# 7SegDisplay.net
KiCad netlist of a schematic drawn in Altium Designer
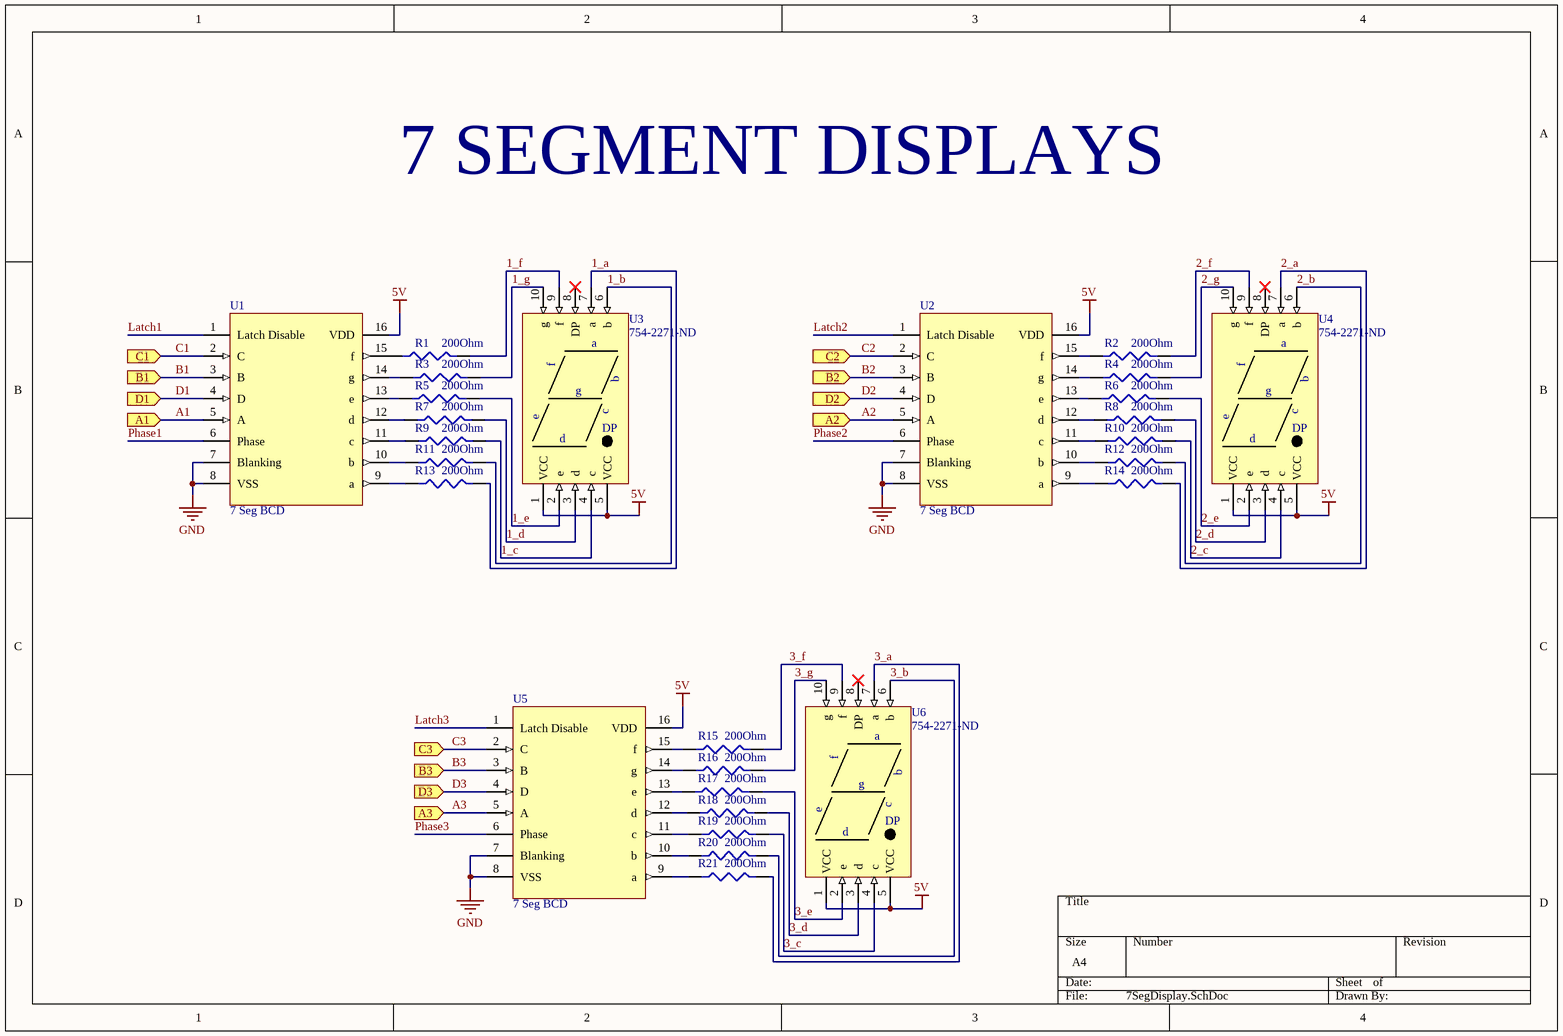
[diagram p0: 7SegDisplay.SchDoc]

(export (version "E")
  (design (tool "Eeschema 10.0.6"))
  (components
    (comp (ref "R1")
      (value "200Ohm")
      (footprint "RES-0805")
      (description "RES SMD 200 OHM 1% 1/4W 0805")
      (fields
        (field (name "MANUFACTURER") "Stackpole Electronics")
        (field (name "MANUFACTURER PART NUMBER") "RNCP0805FTD200R")
      )
      (libsource (lib "Dashboard") (part "RNCP0805FTD200R"))
    )
    (comp (ref "R2")
      (value "200Ohm")
      (footprint "RES-0805")
      (description "RES SMD 200 OHM 1% 1/4W 0805")
      (fields
        (field (name "MANUFACTURER") "Stackpole Electronics")
        (field (name "MANUFACTURER PART NUMBER") "RNCP0805FTD200R")
      )
      (libsource (lib "Dashboard") (part "RNCP0805FTD200R"))
    )
    (comp (ref "R3")
      (value "200Ohm")
      (footprint "RES-0805")
      (description "RES SMD 200 OHM 1% 1/4W 0805")
      (fields
        (field (name "MANUFACTURER") "Stackpole Electronics")
        (field (name "MANUFACTURER PART NUMBER") "RNCP0805FTD200R")
      )
      (libsource (lib "Dashboard") (part "RNCP0805FTD200R"))
    )
    (comp (ref "R4")
      (value "200Ohm")
      (footprint "RES-0805")
      (description "RES SMD 200 OHM 1% 1/4W 0805")
      (fields
        (field (name "MANUFACTURER") "Stackpole Electronics")
        (field (name "MANUFACTURER PART NUMBER") "RNCP0805FTD200R")
      )
      (libsource (lib "Dashboard") (part "RNCP0805FTD200R"))
    )
    (comp (ref "R5")
      (value "200Ohm")
      (footprint "RES-0805")
      (description "RES SMD 200 OHM 1% 1/4W 0805")
      (fields
        (field (name "MANUFACTURER") "Stackpole Electronics")
        (field (name "MANUFACTURER PART NUMBER") "RNCP0805FTD200R")
      )
      (libsource (lib "Dashboard") (part "RNCP0805FTD200R"))
    )
    (comp (ref "R6")
      (value "200Ohm")
      (footprint "RES-0805")
      (description "RES SMD 200 OHM 1% 1/4W 0805")
      (fields
        (field (name "MANUFACTURER") "Stackpole Electronics")
        (field (name "MANUFACTURER PART NUMBER") "RNCP0805FTD200R")
      )
      (libsource (lib "Dashboard") (part "RNCP0805FTD200R"))
    )
    (comp (ref "R7")
      (value "200Ohm")
      (footprint "RES-0805")
      (description "RES SMD 200 OHM 1% 1/4W 0805")
      (fields
        (field (name "MANUFACTURER") "Stackpole Electronics")
        (field (name "MANUFACTURER PART NUMBER") "RNCP0805FTD200R")
      )
      (libsource (lib "Dashboard") (part "RNCP0805FTD200R"))
    )
    (comp (ref "R8")
      (value "200Ohm")
      (footprint "RES-0805")
      (description "RES SMD 200 OHM 1% 1/4W 0805")
      (fields
        (field (name "MANUFACTURER") "Stackpole Electronics")
        (field (name "MANUFACTURER PART NUMBER") "RNCP0805FTD200R")
      )
      (libsource (lib "Dashboard") (part "RNCP0805FTD200R"))
    )
    (comp (ref "R9")
      (value "200Ohm")
      (footprint "RES-0805")
      (description "RES SMD 200 OHM 1% 1/4W 0805")
      (fields
        (field (name "MANUFACTURER") "Stackpole Electronics")
        (field (name "MANUFACTURER PART NUMBER") "RNCP0805FTD200R")
      )
      (libsource (lib "Dashboard") (part "RNCP0805FTD200R"))
    )
    (comp (ref "R10")
      (value "200Ohm")
      (footprint "RES-0805")
      (description "RES SMD 200 OHM 1% 1/4W 0805")
      (fields
        (field (name "MANUFACTURER") "Stackpole Electronics")
        (field (name "MANUFACTURER PART NUMBER") "RNCP0805FTD200R")
      )
      (libsource (lib "Dashboard") (part "RNCP0805FTD200R"))
    )
    (comp (ref "R11")
      (value "200Ohm")
      (footprint "RES-0805")
      (description "RES SMD 200 OHM 1% 1/4W 0805")
      (fields
        (field (name "MANUFACTURER") "Stackpole Electronics")
        (field (name "MANUFACTURER PART NUMBER") "RNCP0805FTD200R")
      )
      (libsource (lib "Dashboard") (part "RNCP0805FTD200R"))
    )
    (comp (ref "R12")
      (value "200Ohm")
      (footprint "RES-0805")
      (description "RES SMD 200 OHM 1% 1/4W 0805")
      (fields
        (field (name "MANUFACTURER") "Stackpole Electronics")
        (field (name "MANUFACTURER PART NUMBER") "RNCP0805FTD200R")
      )
      (libsource (lib "Dashboard") (part "RNCP0805FTD200R"))
    )
    (comp (ref "R13")
      (value "200Ohm")
      (footprint "RES-0805")
      (description "RES SMD 200 OHM 1% 1/4W 0805")
      (fields
        (field (name "MANUFACTURER") "Stackpole Electronics")
        (field (name "MANUFACTURER PART NUMBER") "RNCP0805FTD200R")
      )
      (libsource (lib "Dashboard") (part "RNCP0805FTD200R"))
    )
    (comp (ref "R14")
      (value "200Ohm")
      (footprint "RES-0805")
      (description "RES SMD 200 OHM 1% 1/4W 0805")
      (fields
        (field (name "MANUFACTURER") "Stackpole Electronics")
        (field (name "MANUFACTURER PART NUMBER") "RNCP0805FTD200R")
      )
      (libsource (lib "Dashboard") (part "RNCP0805FTD200R"))
    )
    (comp (ref "R15")
      (value "200Ohm")
      (footprint "RES-0805")
      (description "RES SMD 200 OHM 1% 1/4W 0805")
      (fields
        (field (name "MANUFACTURER") "Stackpole Electronics")
        (field (name "MANUFACTURER PART NUMBER") "RNCP0805FTD200R")
      )
      (libsource (lib "Dashboard") (part "RNCP0805FTD200R"))
    )
    (comp (ref "R16")
      (value "200Ohm")
      (footprint "RES-0805")
      (description "RES SMD 200 OHM 1% 1/4W 0805")
      (fields
        (field (name "MANUFACTURER") "Stackpole Electronics")
        (field (name "MANUFACTURER PART NUMBER") "RNCP0805FTD200R")
      )
      (libsource (lib "Dashboard") (part "RNCP0805FTD200R"))
    )
    (comp (ref "R17")
      (value "200Ohm")
      (footprint "RES-0805")
      (description "RES SMD 200 OHM 1% 1/4W 0805")
      (fields
        (field (name "MANUFACTURER") "Stackpole Electronics")
        (field (name "MANUFACTURER PART NUMBER") "RNCP0805FTD200R")
      )
      (libsource (lib "Dashboard") (part "RNCP0805FTD200R"))
    )
    (comp (ref "R18")
      (value "200Ohm")
      (footprint "RES-0805")
      (description "RES SMD 200 OHM 1% 1/4W 0805")
      (fields
        (field (name "MANUFACTURER") "Stackpole Electronics")
        (field (name "MANUFACTURER PART NUMBER") "RNCP0805FTD200R")
      )
      (libsource (lib "Dashboard") (part "RNCP0805FTD200R"))
    )
    (comp (ref "R19")
      (value "200Ohm")
      (footprint "RES-0805")
      (description "RES SMD 200 OHM 1% 1/4W 0805")
      (fields
        (field (name "MANUFACTURER") "Stackpole Electronics")
        (field (name "MANUFACTURER PART NUMBER") "RNCP0805FTD200R")
      )
      (libsource (lib "Dashboard") (part "RNCP0805FTD200R"))
    )
    (comp (ref "R20")
      (value "200Ohm")
      (footprint "RES-0805")
      (description "RES SMD 200 OHM 1% 1/4W 0805")
      (fields
        (field (name "MANUFACTURER") "Stackpole Electronics")
        (field (name "MANUFACTURER PART NUMBER") "RNCP0805FTD200R")
      )
      (libsource (lib "Dashboard") (part "RNCP0805FTD200R"))
    )
    (comp (ref "R21")
      (value "200Ohm")
      (footprint "RES-0805")
      (description "RES SMD 200 OHM 1% 1/4W 0805")
      (fields
        (field (name "MANUFACTURER") "Stackpole Electronics")
        (field (name "MANUFACTURER PART NUMBER") "RNCP0805FTD200R")
      )
      (libsource (lib "Dashboard") (part "RNCP0805FTD200R"))
    )
    (comp (ref "U1")
      (value "7 Seg BCD")
      (footprint "TSOP65P640X120-16N")
      (description "IC BCD7SEG LCH/DECD/DRVR 16TSSOP")
      (fields
        (field (name "MANUFACTURER") "Texas Instruments")
        (field (name "MANUFACTURER PART NUMBER") "CD4543BPWR")
      )
      (libsource (lib "Dashboard") (part "CD4543BPWR"))
    )
    (comp (ref "U2")
      (value "7 Seg BCD")
      (footprint "TSOP65P640X120-16N")
      (description "IC BCD7SEG LCH/DECD/DRVR 16TSSOP")
      (fields
        (field (name "MANUFACTURER") "Texas Instruments")
        (field (name "MANUFACTURER PART NUMBER") "CD4543BPWR")
      )
      (libsource (lib "Dashboard") (part "CD4543BPWR"))
    )
    (comp (ref "U3")
      (value "754-2271-ND")
      (footprint "SA15-11EWA")
      (description "DISPLAY, SEVEN SEGMENT, 47MM, RED, COMMON ANODE")
      (fields
        (field (name "MANUFACTURER") "Kingbright")
        (field (name "MANUFACTURER PART NUMBER") "SA15-11EWA")
      )
      (libsource (lib "Dashboard") (part "SA15-11EWA"))
    )
    (comp (ref "U4")
      (value "754-2271-ND")
      (footprint "SA15-11EWA")
      (description "DISPLAY, SEVEN SEGMENT, 47MM, RED, COMMON ANODE")
      (fields
        (field (name "MANUFACTURER") "Kingbright")
        (field (name "MANUFACTURER PART NUMBER") "SA15-11EWA")
      )
      (libsource (lib "Dashboard") (part "SA15-11EWA"))
    )
    (comp (ref "U5")
      (value "7 Seg BCD")
      (footprint "TSOP65P640X120-16N")
      (description "IC BCD7SEG LCH/DECD/DRVR 16TSSOP")
      (fields
        (field (name "MANUFACTURER") "Texas Instruments")
        (field (name "MANUFACTURER PART NUMBER") "CD4543BPWR")
      )
      (libsource (lib "Dashboard") (part "CD4543BPWR"))
    )
    (comp (ref "U6")
      (value "754-2271-ND")
      (footprint "SA15-11EWA")
      (description "DISPLAY, SEVEN SEGMENT, 47MM, RED, COMMON ANODE")
      (fields
        (field (name "MANUFACTURER") "Kingbright")
        (field (name "MANUFACTURER PART NUMBER") "SA15-11EWA")
      )
      (libsource (lib "Dashboard") (part "SA15-11EWA"))
    )
  )
  (nets
    (net (code "1") (name "/1_a") (class "Default")
      (node (ref "R13") (pin "2") (pinfunction "2_2") (pintype "passive"))
      (node (ref "U3") (pin "7") (pinfunction "a_7") (pintype "input"))
    )
    (net (code "2") (name "/1_b") (class "Default")
      (node (ref "R11") (pin "2") (pinfunction "2_2") (pintype "passive"))
      (node (ref "U3") (pin "6") (pinfunction "b_6") (pintype "input"))
    )
    (net (code "3") (name "/1_c") (class "Default")
      (node (ref "R9") (pin "2") (pinfunction "2_2") (pintype "passive"))
      (node (ref "U3") (pin "4") (pinfunction "c_4") (pintype "input"))
    )
    (net (code "4") (name "/1_d") (class "Default")
      (node (ref "R7") (pin "2") (pinfunction "2_2") (pintype "passive"))
      (node (ref "U3") (pin "3") (pinfunction "d_3") (pintype "input"))
    )
    (net (code "5") (name "/1_e") (class "Default")
      (node (ref "R5") (pin "2") (pinfunction "2_2") (pintype "passive"))
      (node (ref "U3") (pin "2") (pinfunction "e_2") (pintype "input"))
    )
    (net (code "6") (name "/1_f") (class "Default")
      (node (ref "R1") (pin "2") (pinfunction "2_2") (pintype "passive"))
      (node (ref "U3") (pin "9") (pinfunction "f_9") (pintype "input"))
    )
    (net (code "7") (name "/1_g") (class "Default")
      (node (ref "R3") (pin "2") (pinfunction "2_2") (pintype "passive"))
      (node (ref "U3") (pin "10") (pinfunction "g_10") (pintype "input"))
    )
    (net (code "8") (name "/2_a") (class "Default")
      (node (ref "R14") (pin "2") (pinfunction "2_2") (pintype "passive"))
      (node (ref "U4") (pin "7") (pinfunction "a_7") (pintype "input"))
    )
    (net (code "9") (name "/2_b") (class "Default")
      (node (ref "R12") (pin "2") (pinfunction "2_2") (pintype "passive"))
      (node (ref "U4") (pin "6") (pinfunction "b_6") (pintype "input"))
    )
    (net (code "10") (name "/2_c") (class "Default")
      (node (ref "R10") (pin "2") (pinfunction "2_2") (pintype "passive"))
      (node (ref "U4") (pin "4") (pinfunction "c_4") (pintype "input"))
    )
    (net (code "11") (name "/2_d") (class "Default")
      (node (ref "R8") (pin "2") (pinfunction "2_2") (pintype "passive"))
      (node (ref "U4") (pin "3") (pinfunction "d_3") (pintype "input"))
    )
    (net (code "12") (name "/2_e") (class "Default")
      (node (ref "R6") (pin "2") (pinfunction "2_2") (pintype "passive"))
      (node (ref "U4") (pin "2") (pinfunction "e_2") (pintype "input"))
    )
    (net (code "13") (name "/2_f") (class "Default")
      (node (ref "R2") (pin "2") (pinfunction "2_2") (pintype "passive"))
      (node (ref "U4") (pin "9") (pinfunction "f_9") (pintype "input"))
    )
    (net (code "14") (name "/2_g") (class "Default")
      (node (ref "R4") (pin "2") (pinfunction "2_2") (pintype "passive"))
      (node (ref "U4") (pin "10") (pinfunction "g_10") (pintype "input"))
    )
    (net (code "15") (name "/3_a") (class "Default")
      (node (ref "R21") (pin "2") (pinfunction "2_2") (pintype "passive"))
      (node (ref "U6") (pin "7") (pinfunction "a_7") (pintype "input"))
    )
    (net (code "16") (name "/3_b") (class "Default")
      (node (ref "R20") (pin "2") (pinfunction "2_2") (pintype "passive"))
      (node (ref "U6") (pin "6") (pinfunction "b_6") (pintype "input"))
    )
    (net (code "17") (name "/3_c") (class "Default")
      (node (ref "R19") (pin "2") (pinfunction "2_2") (pintype "passive"))
      (node (ref "U6") (pin "4") (pinfunction "c_4") (pintype "input"))
    )
    (net (code "18") (name "/3_d") (class "Default")
      (node (ref "R18") (pin "2") (pinfunction "2_2") (pintype "passive"))
      (node (ref "U6") (pin "3") (pinfunction "d_3") (pintype "input"))
    )
    (net (code "19") (name "/3_e") (class "Default")
      (node (ref "R17") (pin "2") (pinfunction "2_2") (pintype "passive"))
      (node (ref "U6") (pin "2") (pinfunction "e_2") (pintype "input"))
    )
    (net (code "20") (name "/3_f") (class "Default")
      (node (ref "R15") (pin "2") (pinfunction "2_2") (pintype "passive"))
      (node (ref "U6") (pin "9") (pinfunction "f_9") (pintype "input"))
    )
    (net (code "21") (name "/3_g") (class "Default")
      (node (ref "R16") (pin "2") (pinfunction "2_2") (pintype "passive"))
      (node (ref "U6") (pin "10") (pinfunction "g_10") (pintype "input"))
    )
    (net (code "22") (name "/A1") (class "Default")
      (node (ref "U1") (pin "5") (pinfunction "A_5") (pintype "input"))
    )
    (net (code "23") (name "/A2") (class "Default")
      (node (ref "U2") (pin "5") (pinfunction "A_5") (pintype "input"))
    )
    (net (code "24") (name "/A3") (class "Default")
      (node (ref "U5") (pin "5") (pinfunction "A_5") (pintype "input"))
    )
    (net (code "25") (name "/B1") (class "Default")
      (node (ref "U1") (pin "3") (pinfunction "B_3") (pintype "input"))
    )
    (net (code "26") (name "/B2") (class "Default")
      (node (ref "U2") (pin "3") (pinfunction "B_3") (pintype "input"))
    )
    (net (code "27") (name "/B3") (class "Default")
      (node (ref "U5") (pin "3") (pinfunction "B_3") (pintype "input"))
    )
    (net (code "28") (name "/C1") (class "Default")
      (node (ref "U1") (pin "2") (pinfunction "C_2") (pintype "input"))
    )
    (net (code "29") (name "/C2") (class "Default")
      (node (ref "U2") (pin "2") (pinfunction "C_2") (pintype "input"))
    )
    (net (code "30") (name "/C3") (class "Default")
      (node (ref "U5") (pin "2") (pinfunction "C_2") (pintype "input"))
    )
    (net (code "31") (name "/D1") (class "Default")
      (node (ref "U1") (pin "4") (pinfunction "D_4") (pintype "input"))
    )
    (net (code "32") (name "/D2") (class "Default")
      (node (ref "U2") (pin "4") (pinfunction "D_4") (pintype "input"))
    )
    (net (code "33") (name "/D3") (class "Default")
      (node (ref "U5") (pin "4") (pinfunction "D_4") (pintype "input"))
    )
    (net (code "34") (name "/Latch1") (class "Default")
      (node (ref "U1") (pin "1") (pinfunction "Latch_Disable_1") (pintype "power_in"))
    )
    (net (code "35") (name "/Latch2") (class "Default")
      (node (ref "U2") (pin "1") (pinfunction "Latch_Disable_1") (pintype "power_in"))
    )
    (net (code "36") (name "/Latch3") (class "Default")
      (node (ref "U5") (pin "1") (pinfunction "Latch_Disable_1") (pintype "power_in"))
    )
    (net (code "37") (name "/Phase1") (class "Default")
      (node (ref "U1") (pin "6") (pinfunction "Phase_6") (pintype "power_in"))
    )
    (net (code "38") (name "/Phase2") (class "Default")
      (node (ref "U2") (pin "6") (pinfunction "Phase_6") (pintype "power_in"))
    )
    (net (code "39") (name "/Phase3") (class "Default")
      (node (ref "U5") (pin "6") (pinfunction "Phase_6") (pintype "power_in"))
    )
    (net (code "40") (name "5V") (class "Default")
      (node (ref "U1") (pin "16") (pinfunction "VDD_16") (pintype "power_in"))
      (node (ref "U2") (pin "16") (pinfunction "VDD_16") (pintype "power_in"))
      (node (ref "U3") (pin "1") (pinfunction "VCC_1") (pintype "power_in"))
      (node (ref "U3") (pin "5") (pinfunction "VCC_5") (pintype "power_in"))
      (node (ref "U4") (pin "1") (pinfunction "VCC_1") (pintype "power_in"))
      (node (ref "U4") (pin "5") (pinfunction "VCC_5") (pintype "power_in"))
      (node (ref "U5") (pin "16") (pinfunction "VDD_16") (pintype "power_in"))
      (node (ref "U6") (pin "1") (pinfunction "VCC_1") (pintype "power_in"))
      (node (ref "U6") (pin "5") (pinfunction "VCC_5") (pintype "power_in"))
    )
    (net (code "41") (name "GND") (class "Default")
      (node (ref "U1") (pin "7") (pinfunction "Blanking_7") (pintype "power_in"))
      (node (ref "U1") (pin "8") (pinfunction "VSS_8") (pintype "power_in"))
      (node (ref "U2") (pin "7") (pinfunction "Blanking_7") (pintype "power_in"))
      (node (ref "U2") (pin "8") (pinfunction "VSS_8") (pintype "power_in"))
      (node (ref "U5") (pin "7") (pinfunction "Blanking_7") (pintype "power_in"))
      (node (ref "U5") (pin "8") (pinfunction "VSS_8") (pintype "power_in"))
    )
    (net (code "42") (name "Net-(U1-a)") (class "Default")
      (node (ref "R13") (pin "1") (pinfunction "1_1") (pintype "passive"))
      (node (ref "U1") (pin "9") (pinfunction "a_9") (pintype "output"))
    )
    (net (code "43") (name "Net-(U1-b)") (class "Default")
      (node (ref "R11") (pin "1") (pinfunction "1_1") (pintype "passive"))
      (node (ref "U1") (pin "10") (pinfunction "b_10") (pintype "output"))
    )
    (net (code "44") (name "Net-(U1-c)") (class "Default")
      (node (ref "R9") (pin "1") (pinfunction "1_1") (pintype "passive"))
      (node (ref "U1") (pin "11") (pinfunction "c_11") (pintype "output"))
    )
    (net (code "45") (name "Net-(U1-d)") (class "Default")
      (node (ref "R7") (pin "1") (pinfunction "1_1") (pintype "passive"))
      (node (ref "U1") (pin "12") (pinfunction "d_12") (pintype "output"))
    )
    (net (code "46") (name "Net-(U1-e)") (class "Default")
      (node (ref "R5") (pin "1") (pinfunction "1_1") (pintype "passive"))
      (node (ref "U1") (pin "13") (pinfunction "e_13") (pintype "output"))
    )
    (net (code "47") (name "Net-(U1-f)") (class "Default")
      (node (ref "R1") (pin "1") (pinfunction "1_1") (pintype "passive"))
      (node (ref "U1") (pin "15") (pinfunction "f_15") (pintype "output"))
    )
    (net (code "48") (name "Net-(U1-g)") (class "Default")
      (node (ref "R3") (pin "1") (pinfunction "1_1") (pintype "passive"))
      (node (ref "U1") (pin "14") (pinfunction "g_14") (pintype "output"))
    )
    (net (code "49") (name "Net-(U2-a)") (class "Default")
      (node (ref "R14") (pin "1") (pinfunction "1_1") (pintype "passive"))
      (node (ref "U2") (pin "9") (pinfunction "a_9") (pintype "output"))
    )
    (net (code "50") (name "Net-(U2-b)") (class "Default")
      (node (ref "R12") (pin "1") (pinfunction "1_1") (pintype "passive"))
      (node (ref "U2") (pin "10") (pinfunction "b_10") (pintype "output"))
    )
    (net (code "51") (name "Net-(U2-c)") (class "Default")
      (node (ref "R10") (pin "1") (pinfunction "1_1") (pintype "passive"))
      (node (ref "U2") (pin "11") (pinfunction "c_11") (pintype "output"))
    )
    (net (code "52") (name "Net-(U2-d)") (class "Default")
      (node (ref "R8") (pin "1") (pinfunction "1_1") (pintype "passive"))
      (node (ref "U2") (pin "12") (pinfunction "d_12") (pintype "output"))
    )
    (net (code "53") (name "Net-(U2-e)") (class "Default")
      (node (ref "R6") (pin "1") (pinfunction "1_1") (pintype "passive"))
      (node (ref "U2") (pin "13") (pinfunction "e_13") (pintype "output"))
    )
    (net (code "54") (name "Net-(U2-f)") (class "Default")
      (node (ref "R2") (pin "1") (pinfunction "1_1") (pintype "passive"))
      (node (ref "U2") (pin "15") (pinfunction "f_15") (pintype "output"))
    )
    (net (code "55") (name "Net-(U2-g)") (class "Default")
      (node (ref "R4") (pin "1") (pinfunction "1_1") (pintype "passive"))
      (node (ref "U2") (pin "14") (pinfunction "g_14") (pintype "output"))
    )
    (net (code "56") (name "Net-(U5-a)") (class "Default")
      (node (ref "R21") (pin "1") (pinfunction "1_1") (pintype "passive"))
      (node (ref "U5") (pin "9") (pinfunction "a_9") (pintype "output"))
    )
    (net (code "57") (name "Net-(U5-b)") (class "Default")
      (node (ref "R20") (pin "1") (pinfunction "1_1") (pintype "passive"))
      (node (ref "U5") (pin "10") (pinfunction "b_10") (pintype "output"))
    )
    (net (code "58") (name "Net-(U5-c)") (class "Default")
      (node (ref "R19") (pin "1") (pinfunction "1_1") (pintype "passive"))
      (node (ref "U5") (pin "11") (pinfunction "c_11") (pintype "output"))
    )
    (net (code "59") (name "Net-(U5-d)") (class "Default")
      (node (ref "R18") (pin "1") (pinfunction "1_1") (pintype "passive"))
      (node (ref "U5") (pin "12") (pinfunction "d_12") (pintype "output"))
    )
    (net (code "60") (name "Net-(U5-e)") (class "Default")
      (node (ref "R17") (pin "1") (pinfunction "1_1") (pintype "passive"))
      (node (ref "U5") (pin "13") (pinfunction "e_13") (pintype "output"))
    )
    (net (code "61") (name "Net-(U5-f)") (class "Default")
      (node (ref "R15") (pin "1") (pinfunction "1_1") (pintype "passive"))
      (node (ref "U5") (pin "15") (pinfunction "f_15") (pintype "output"))
    )
    (net (code "62") (name "Net-(U5-g)") (class "Default")
      (node (ref "R16") (pin "1") (pinfunction "1_1") (pintype "passive"))
      (node (ref "U5") (pin "14") (pinfunction "g_14") (pintype "output"))
    )
    (net (code "63") (name "unconnected-(U3-DP-Pad8)") (class "Default")
      (node (ref "U3") (pin "8") (pinfunction "DP_8") (pintype "input+no_connect"))
    )
    (net (code "64") (name "unconnected-(U4-DP-Pad8)") (class "Default")
      (node (ref "U4") (pin "8") (pinfunction "DP_8") (pintype "input+no_connect"))
    )
    (net (code "65") (name "unconnected-(U6-DP-Pad8)") (class "Default")
      (node (ref "U6") (pin "8") (pinfunction "DP_8") (pintype "input+no_connect"))
    )
  )
)
